# SCH_Placa-Central-Drone_2026-04-25.net
KiCad netlist of a schematic drawn in EasyEDA
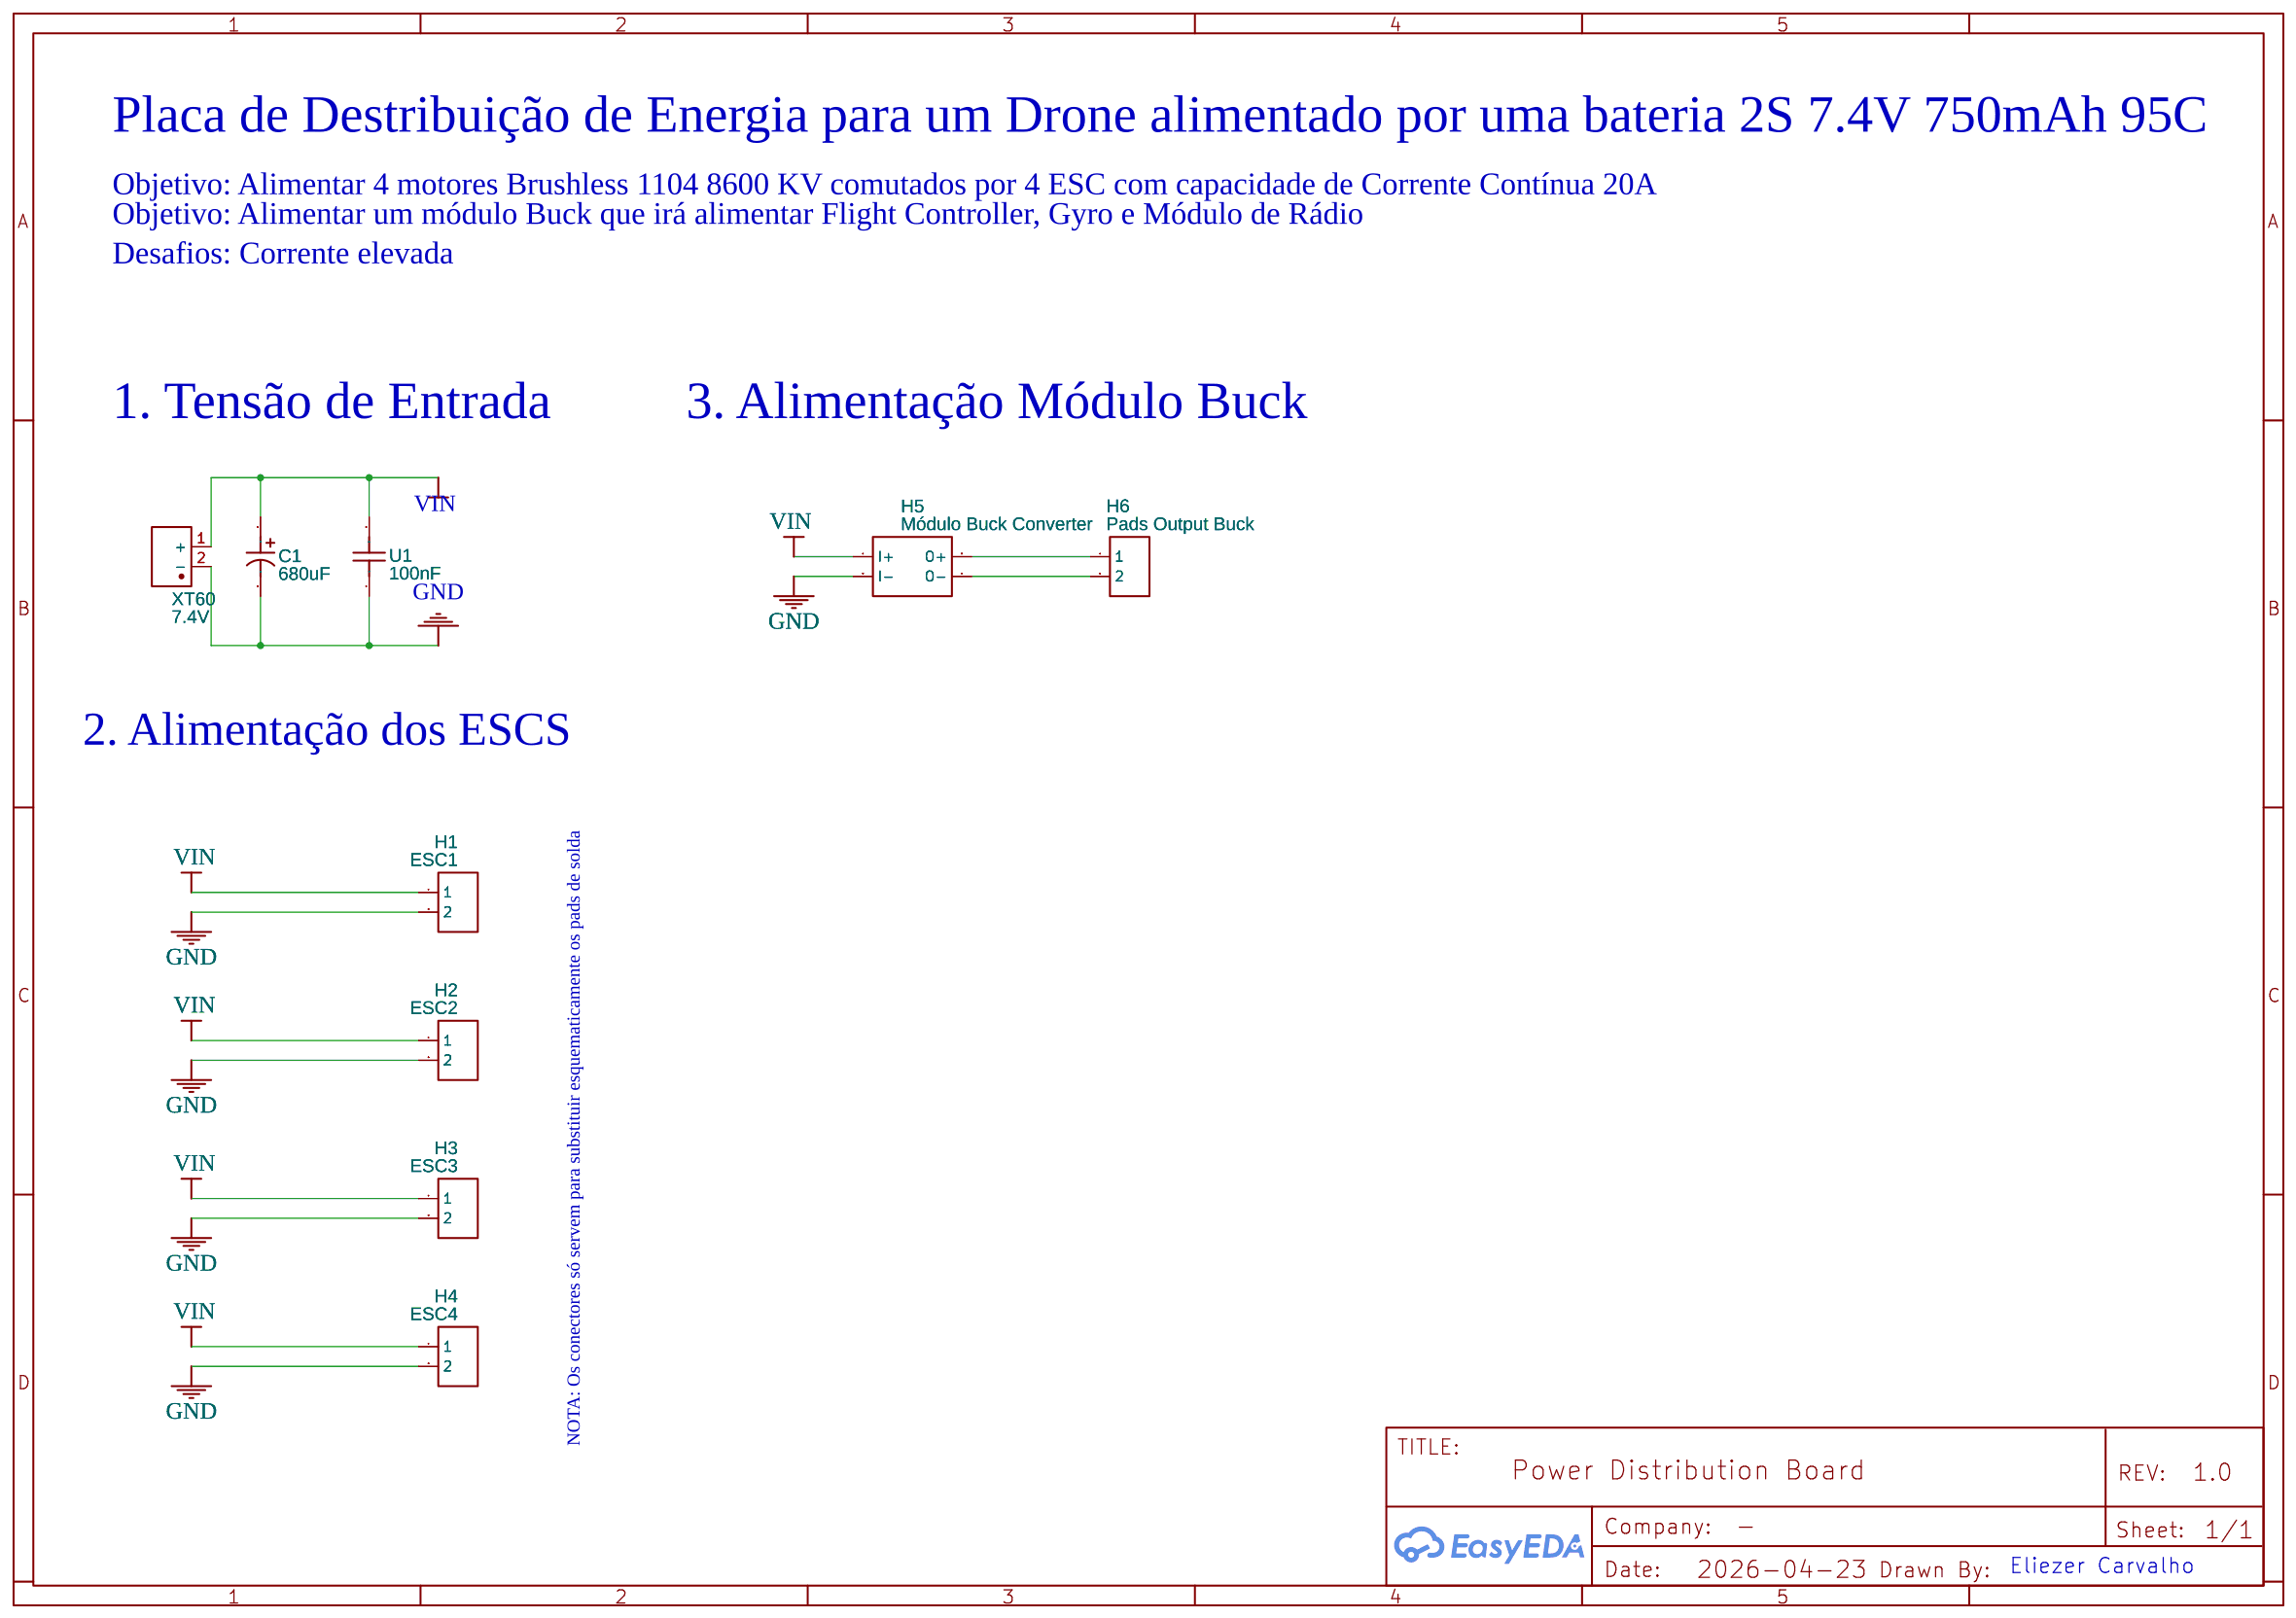
[diagram p0: schematic sheet]

(export (version "E")
  (design (tool "Eeschema 10.0.6"))
  (components
    (comp (ref "7.4V")
      (value "XT60")
      (fields (field (name "Manufacturer Part") "XT60-M.") (field (name "Manufacturer") "AMASS(艾迈斯)"))
      (libsource (lib "") (part "XT60"))
    )
    (comp (ref "C1")
      (value "680uF")
      (fields
        (field (name "Manufacturer Part") "ENB1EM471G13OTH")
        (field (name "Manufacturer") "https://mauser.pt/004-1414/condensador-electrolitico-low-esr-680uf-25v-105-10x16mm")
      )
      (libsource (lib "") (part "ENB1EM471G13OTH"))
    )
    (comp (ref "H1") (value "ESC1") (libsource (lib "") (part "HDR-F-2.54_1x2")))
    (comp (ref "H2") (value "ESC2") (libsource (lib "") (part "HDR-F-2.54_1x2")))
    (comp (ref "H3") (value "ESC3") (libsource (lib "") (part "HDR-F-2.54_1x2")))
    (comp (ref "H4") (value "ESC4") (libsource (lib "") (part "HDR-F-2.54_1x2")))
    (comp (ref "H5") (value "Módulo Buck Converter") (libsource (lib "") (part "HDR-F-2.54_2x2")))
    (comp (ref "H6") (value "Pads Output Buck") (libsource (lib "") (part "HDR-F-2.54_1x2")))
    (comp (ref "U1")
      (value "100nF")
      (fields
        (field (name "Manufacturer Part") "178MU0013")
        (field (name "Manufacturer") "https://mauser.pt/004-5086/condensador-ceramico-100nf-50v")
      )
      (libsource (lib "") (part "178MU0013"))
    )
  )
  (nets
    (net (code "1") (name "GND") (class "Default")
      (node (ref "7.4V") (pin "2") (pinfunction "-_2") (pintype "unspecified"))
      (node (ref "C1") (pin "2") (pinfunction "2_2") (pintype "input"))
      (node (ref "H1") (pin "2") (pinfunction "2_2") (pintype "input"))
      (node (ref "H2") (pin "2") (pinfunction "2_2") (pintype "input"))
      (node (ref "H3") (pin "2") (pinfunction "2_2") (pintype "input"))
      (node (ref "H4") (pin "2") (pinfunction "2_2") (pintype "input"))
      (node (ref "H5") (pin "3") (pinfunction "I-_3") (pintype "unspecified"))
      (node (ref "U1") (pin "1") (pinfunction "1_1") (pintype "unspecified"))
    )
    (net (code "2") (name "Net-(H5-O+)") (class "Default")
      (node (ref "H5") (pin "2") (pinfunction "O+_2") (pintype "unspecified"))
      (node (ref "H6") (pin "1") (pinfunction "1_1") (pintype "input"))
    )
    (net (code "3") (name "Net-(H5-O-)") (class "Default")
      (node (ref "H5") (pin "4") (pinfunction "O-_4") (pintype "unspecified"))
      (node (ref "H6") (pin "2") (pinfunction "2_2") (pintype "input"))
    )
    (net (code "4") (name "VIN") (class "Default")
      (node (ref "7.4V") (pin "1") (pinfunction "+_1") (pintype "unspecified"))
      (node (ref "C1") (pin "1") (pinfunction "1_1") (pintype "input"))
      (node (ref "H1") (pin "1") (pinfunction "1_1") (pintype "input"))
      (node (ref "H2") (pin "1") (pinfunction "1_1") (pintype "input"))
      (node (ref "H3") (pin "1") (pinfunction "1_1") (pintype "input"))
      (node (ref "H4") (pin "1") (pinfunction "1_1") (pintype "input"))
      (node (ref "H5") (pin "1") (pinfunction "I+_1") (pintype "unspecified"))
      (node (ref "U1") (pin "2") (pinfunction "2_2") (pintype "unspecified"))
    )
  )
)
